# Main.net
KiCad netlist of a schematic drawn in Altium Designer
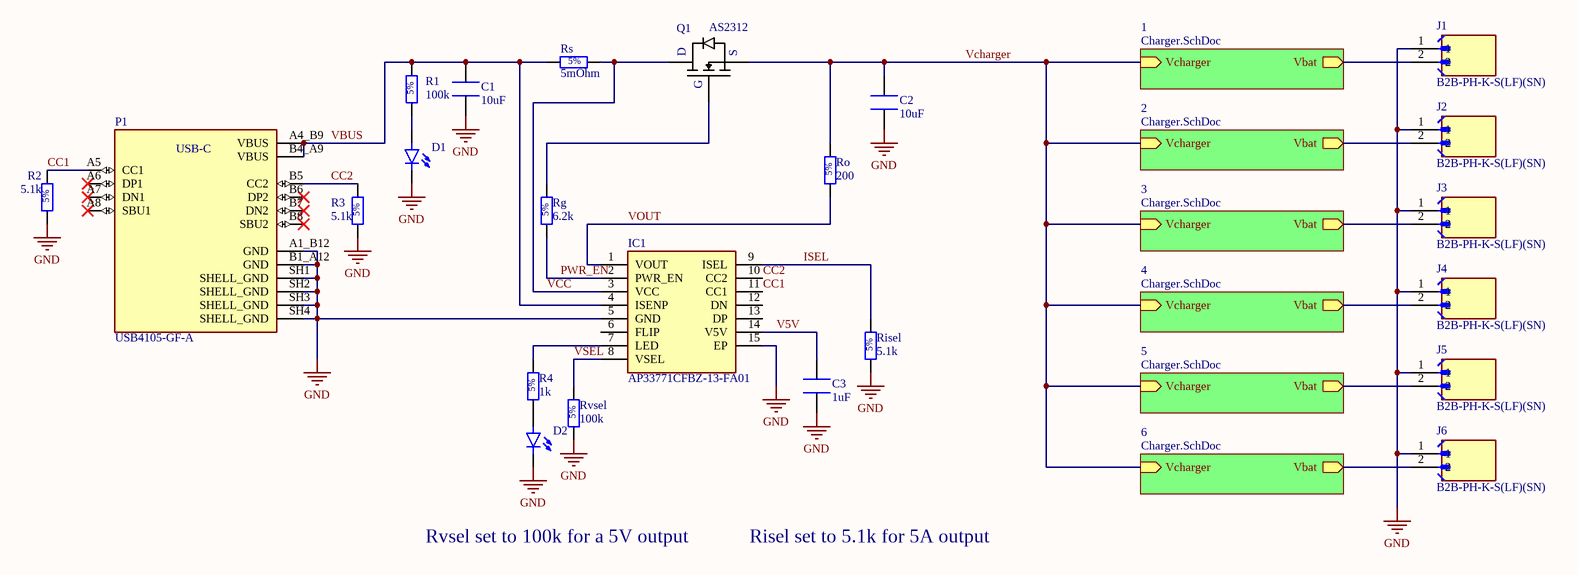
[diagram p0: Main.SchDoc]

(export (version "E")
  (design (tool "Eeschema 10.0.6"))
  (components
    (comp (ref "C1")
      (value "10uF")
      (footprint "APSS Flight Parts:CAPACITOR_0805_2012M-70N")
      (fields
        (field (name "TOLERANCE") "±20%")
        (field (name "MF PART NO.") "GRM21BR60J107ME15L")
        (field (name "APSS STANDARD PART") "APSS Standard")
      )
      (libsource (lib "APSS Flight Parts") (part "GRM21BR60J107ME15L"))
    )
    (comp (ref "C2")
      (value "10uF")
      (footprint "APSS Flight Parts:CAPACITOR_0805_2012M-70N")
      (fields
        (field (name "TOLERANCE") "±20%")
        (field (name "MF PART NO.") "GRM21BR60J107ME15L")
        (field (name "APSS STANDARD PART") "APSS Standard")
      )
      (libsource (lib "APSS Flight Parts") (part "GRM21BR60J107ME15L"))
    )
    (comp (ref "C3")
      (value "1uF")
      (footprint "APSS Flight Parts:CAPACITOR_0805_2012M-70N")
      (fields
        (field (name "TOLERANCE") "±20%")
        (field (name "MF PART NO.") "GRM21BR60J107ME15L")
        (field (name "APSS STANDARD PART") "APSS Standard")
      )
      (libsource (lib "APSS Flight Parts") (part "GRM21BR60J107ME15L"))
    )
    (comp (ref "D1")
      (value "LTST-C190 Series")
      (footprint "APSS Prototype Parts:LED_0603_1608M_0.80mm")
      (description "Diode - LED, 0603")
      (fields (field (name "APSS STANDARD PART") "APSS Standard"))
      (libsource (lib "APSS Prototype Parts") (part "LTST-C190 Series"))
    )
    (comp (ref "D2")
      (value "LTST-C190 Series")
      (footprint "APSS Prototype Parts:LED_0603_1608M_0.80mm")
      (description "Diode - LED, 0603")
      (fields (field (name "APSS STANDARD PART") "APSS Standard"))
      (libsource (lib "APSS Prototype Parts") (part "LTST-C190 Series"))
    )
    (comp (ref "IC1")
      (value "AP33771CFBZ-13-FA01")
      (footprint "AP33771CFBZ-13-FA01:AP33771CFBZ13FA01")
      (description "Integrated Circuit")
      (fields (field (name "MOUSER PART NUMBER") "621-P33771CFBZ13FA01"))
      (libsource (lib "AP33771CFBZ-13-FA01") (part "AP33771CFBZ-13-FA01"))
    )
    (comp (ref "J1")
      (value "B2B-PH-K-S(LF)(SN)")
      (footprint "JST_B2B-PH-K-S(LF)(SN)")
      (description "Connector Header Through Hole 2 position 0.079 (2.00mm)")
      (fields (field (name "MF") "JST") (field (name "MP") "B2B-PH-K-S (LF)(SN)"))
      (libsource (lib "B2B-PH-K-S(LF)(SN)") (part "B2B-PH-K-S(LF)(SN)"))
    )
    (comp (ref "J2")
      (value "B2B-PH-K-S(LF)(SN)")
      (footprint "JST_B2B-PH-K-S(LF)(SN)")
      (description "Connector Header Through Hole 2 position 0.079 (2.00mm)")
      (fields (field (name "MF") "JST") (field (name "MP") "B2B-PH-K-S (LF)(SN)"))
      (libsource (lib "B2B-PH-K-S(LF)(SN)") (part "B2B-PH-K-S(LF)(SN)"))
    )
    (comp (ref "J3")
      (value "B2B-PH-K-S(LF)(SN)")
      (footprint "JST_B2B-PH-K-S(LF)(SN)")
      (description "Connector Header Through Hole 2 position 0.079 (2.00mm)")
      (fields (field (name "MF") "JST") (field (name "MP") "B2B-PH-K-S (LF)(SN)"))
      (libsource (lib "B2B-PH-K-S(LF)(SN)") (part "B2B-PH-K-S(LF)(SN)"))
    )
    (comp (ref "J4")
      (value "B2B-PH-K-S(LF)(SN)")
      (footprint "JST_B2B-PH-K-S(LF)(SN)")
      (description "Connector Header Through Hole 2 position 0.079 (2.00mm)")
      (fields (field (name "MF") "JST") (field (name "MP") "B2B-PH-K-S (LF)(SN)"))
      (libsource (lib "B2B-PH-K-S(LF)(SN)") (part "B2B-PH-K-S(LF)(SN)"))
    )
    (comp (ref "J5")
      (value "B2B-PH-K-S(LF)(SN)")
      (footprint "JST_B2B-PH-K-S(LF)(SN)")
      (description "Connector Header Through Hole 2 position 0.079 (2.00mm)")
      (fields (field (name "MF") "JST") (field (name "MP") "B2B-PH-K-S (LF)(SN)"))
      (libsource (lib "B2B-PH-K-S(LF)(SN)") (part "B2B-PH-K-S(LF)(SN)"))
    )
    (comp (ref "J6")
      (value "B2B-PH-K-S(LF)(SN)")
      (footprint "JST_B2B-PH-K-S(LF)(SN)")
      (description "Connector Header Through Hole 2 position 0.079 (2.00mm)")
      (fields (field (name "MF") "JST") (field (name "MP") "B2B-PH-K-S (LF)(SN)"))
      (libsource (lib "B2B-PH-K-S(LF)(SN)") (part "B2B-PH-K-S(LF)(SN)"))
    )
    (comp (ref "P1")
      (value "USB4105-GF-A")
      (footprint "GCT_USB4105-GF-A")
      (libsource (lib "USB4105-GF-A") (part "USB4105-GF-A"))
    )
    (comp (ref "Q1")
      (value "AS2312")
      (footprint "APSS Prototype Parts:SOT23-3N-1.15mm")
      (description "Transistor - MOSFET, N-Channel AS2312")
      (fields (field (name "POWER") "1.2W") (field (name "APSS STANDARD PART") "APSS Standard"))
      (libsource (lib "APSS Prototype Parts") (part "AS2312"))
    )
    (comp (ref "R1")
      (value "100k")
      (footprint "APSS Flight Parts:Resistor_0805_2012M-50N")
      (fields
        (field (name "TOLERANCE") "5%")
        (field (name "POWER") "1/8W")
        (field (name "APSS STANDARD PART") "APSS Standard")
      )
      (libsource (lib "") (part "RMCF0805JT Series_1"))
    )
    (comp (ref "R2")
      (value "5.1k")
      (footprint "APSS Prototype Parts:Resistor_0805_2012M-50N")
      (fields
        (field (name "TOLERANCE") "5%")
        (field (name "POWER") "1/8W")
        (field (name "APSS STANDARD PART") "APSS Standard")
      )
      (libsource (lib "APSS Prototype Parts") (part "RMCF0805JT Series"))
    )
    (comp (ref "R3")
      (value "5.1k")
      (footprint "APSS Prototype Parts:Resistor_0805_2012M-50N")
      (fields
        (field (name "TOLERANCE") "5%")
        (field (name "POWER") "1/8W")
        (field (name "APSS STANDARD PART") "APSS Standard")
      )
      (libsource (lib "APSS Prototype Parts") (part "RMCF0805JT Series"))
    )
    (comp (ref "R4")
      (value "1k")
      (footprint "APSS Flight Parts:Resistor_0805_2012M-50N")
      (fields
        (field (name "TOLERANCE") "5%")
        (field (name "POWER") "1/8W")
        (field (name "APSS STANDARD PART") "APSS Standard")
      )
      (libsource (lib "") (part "RMCF0805JT Series_1"))
    )
    (comp (ref "Rg")
      (value "6.2k")
      (footprint "APSS Flight Parts:Resistor_0805_2012M-50N")
      (fields
        (field (name "TOLERANCE") "5%")
        (field (name "POWER") "1/8W")
        (field (name "APSS STANDARD PART") "APSS Standard")
      )
      (libsource (lib "") (part "RMCF0805JT Series_1"))
    )
    (comp (ref "Risel")
      (value "5.1k")
      (footprint "APSS Flight Parts:Resistor_0805_2012M-50N")
      (fields
        (field (name "TOLERANCE") "5%")
        (field (name "POWER") "1/8W")
        (field (name "APSS STANDARD PART") "APSS Standard")
      )
      (libsource (lib "") (part "RMCF0805JT Series_1"))
    )
    (comp (ref "Ro")
      (value "200")
      (footprint "APSS Flight Parts:Resistor_0805_2012M-50N")
      (fields
        (field (name "TOLERANCE") "5%")
        (field (name "POWER") "1/8W")
        (field (name "APSS STANDARD PART") "APSS Standard")
      )
      (libsource (lib "") (part "RMCF0805JT Series_1"))
    )
    (comp (ref "Rs")
      (value "5mOhm")
      (footprint "APSS Flight Parts:Resistor_0805_2012M-50N")
      (fields
        (field (name "TOLERANCE") "5%")
        (field (name "POWER") "1/8W")
        (field (name "APSS STANDARD PART") "APSS Standard")
      )
      (libsource (lib "APSS Flight Parts") (part "RMCF0805JT Series"))
    )
    (comp (ref "Rvsel")
      (value "100k")
      (footprint "APSS Flight Parts:Resistor_0805_2012M-50N")
      (fields
        (field (name "TOLERANCE") "5%")
        (field (name "POWER") "1/8W")
        (field (name "APSS STANDARD PART") "APSS Standard")
      )
      (libsource (lib "") (part "RMCF0805JT Series_1"))
    )
  )
  (nets
    (net (code "1") (name "/CC1") (class "Default")
      (node (ref "IC1") (pin "11") (pinfunction "CC1_11") (pintype "passive"))
      (node (ref "P1") (pin "A5") (pinfunction "CC1_A5") (pintype "bidirectional"))
      (node (ref "R2") (pin "2") (pinfunction "2_2") (pintype "passive"))
    )
    (net (code "2") (name "/CC2") (class "Default")
      (node (ref "IC1") (pin "10") (pinfunction "CC2_10") (pintype "passive"))
      (node (ref "P1") (pin "B5") (pinfunction "CC2_B5") (pintype "bidirectional"))
      (node (ref "R3") (pin "2") (pinfunction "2_2") (pintype "passive"))
    )
    (net (code "3") (name "/ISEL") (class "Default")
      (node (ref "IC1") (pin "9") (pinfunction "ISEL_9") (pintype "passive"))
      (node (ref "Risel") (pin "2") (pinfunction "2_2") (pintype "passive"))
    )
    (net (code "4") (name "/PWR_EN") (class "Default")
      (node (ref "IC1") (pin "2") (pinfunction "PWR_EN_2") (pintype "passive"))
      (node (ref "Rg") (pin "1") (pinfunction "1_1") (pintype "passive"))
    )
    (net (code "5") (name "/V5V") (class "Default")
      (node (ref "C3") (pin "2") (pinfunction "2_2") (pintype "passive"))
      (node (ref "IC1") (pin "14") (pinfunction "V5V_14") (pintype "passive"))
    )
    (net (code "6") (name "/VBUS") (class "Default")
      (node (ref "C1") (pin "2") (pinfunction "2_2") (pintype "passive"))
      (node (ref "IC1") (pin "4") (pinfunction "ISENP_4") (pintype "passive"))
      (node (ref "P1") (pin "A4_B9") (pinfunction "VBUS_A4_B9") (pintype "power_in"))
      (node (ref "P1") (pin "B4_A9") (pinfunction "VBUS_B4_A9") (pintype "power_in"))
      (node (ref "R1") (pin "2") (pinfunction "2_2") (pintype "passive"))
      (node (ref "Rs") (pin "1") (pinfunction "1_1") (pintype "passive"))
    )
    (net (code "7") (name "/VCC") (class "Default")
      (node (ref "IC1") (pin "3") (pinfunction "VCC_3") (pintype "passive"))
      (node (ref "Q1") (pin "3") (pinfunction "D_3") (pintype "passive"))
      (node (ref "Rs") (pin "2") (pinfunction "2_2") (pintype "passive"))
    )
    (net (code "8") (name "/VOUT") (class "Default")
      (node (ref "IC1") (pin "1") (pinfunction "VOUT_1") (pintype "passive"))
      (node (ref "Ro") (pin "1") (pinfunction "1_1") (pintype "passive"))
    )
    (net (code "9") (name "/VSEL") (class "Default")
      (node (ref "IC1") (pin "8") (pinfunction "VSEL_8") (pintype "passive"))
      (node (ref "Rvsel") (pin "2") (pinfunction "2_2") (pintype "passive"))
    )
    (net (code "10") (name "/Vbat") (class "Default")
      (node (ref "J6") (pin "2") (pinfunction "2_2") (pintype "passive"))
    )
    (net (code "11") (name "/Vbat_1") (class "Default")
      (node (ref "J4") (pin "2") (pinfunction "2_2") (pintype "passive"))
    )
    (net (code "12") (name "/Vbat_2") (class "Default")
      (node (ref "J3") (pin "2") (pinfunction "2_2") (pintype "passive"))
    )
    (net (code "13") (name "/Vbat_3") (class "Default")
      (node (ref "J5") (pin "2") (pinfunction "2_2") (pintype "passive"))
    )
    (net (code "14") (name "/Vbat_4") (class "Default")
      (node (ref "J2") (pin "2") (pinfunction "2_2") (pintype "passive"))
    )
    (net (code "15") (name "/Vbat_5") (class "Default")
      (node (ref "J1") (pin "2") (pinfunction "2_2") (pintype "passive"))
    )
    (net (code "16") (name "/Vcharger") (class "Default")
      (node (ref "C2") (pin "2") (pinfunction "2_2") (pintype "passive"))
      (node (ref "Q1") (pin "2") (pinfunction "S_2") (pintype "passive"))
      (node (ref "Ro") (pin "2") (pinfunction "2_2") (pintype "passive"))
    )
    (net (code "17") (name "GND") (class "Default")
      (node (ref "C1") (pin "1") (pinfunction "1_1") (pintype "passive"))
      (node (ref "C2") (pin "1") (pinfunction "1_1") (pintype "passive"))
      (node (ref "C3") (pin "1") (pinfunction "1_1") (pintype "passive"))
      (node (ref "D1") (pin "C") (pinfunction "C_C") (pintype "passive"))
      (node (ref "D2") (pin "C") (pinfunction "C_C") (pintype "passive"))
      (node (ref "IC1") (pin "15") (pinfunction "EP_15") (pintype "passive"))
      (node (ref "IC1") (pin "5") (pinfunction "GND_5") (pintype "passive"))
      (node (ref "J1") (pin "1") (pinfunction "1_1") (pintype "passive"))
      (node (ref "J2") (pin "1") (pinfunction "1_1") (pintype "passive"))
      (node (ref "J3") (pin "1") (pinfunction "1_1") (pintype "passive"))
      (node (ref "J4") (pin "1") (pinfunction "1_1") (pintype "passive"))
      (node (ref "J5") (pin "1") (pinfunction "1_1") (pintype "passive"))
      (node (ref "J6") (pin "1") (pinfunction "1_1") (pintype "passive"))
      (node (ref "P1") (pin "A1_B12") (pinfunction "GND_A1_B12") (pintype "power_in"))
      (node (ref "P1") (pin "B1_A12") (pinfunction "GND_B1_A12") (pintype "power_in"))
      (node (ref "P1") (pin "SH1") (pinfunction "SHELL_GND_SH1") (pintype "power_in"))
      (node (ref "P1") (pin "SH2") (pinfunction "SHELL_GND_SH2") (pintype "power_in"))
      (node (ref "P1") (pin "SH3") (pinfunction "SHELL_GND_SH3") (pintype "power_in"))
      (node (ref "P1") (pin "SH4") (pinfunction "SHELL_GND_SH4") (pintype "power_in"))
      (node (ref "R2") (pin "1") (pinfunction "1_1") (pintype "passive"))
      (node (ref "R3") (pin "1") (pinfunction "1_1") (pintype "passive"))
      (node (ref "Risel") (pin "1") (pinfunction "1_1") (pintype "passive"))
      (node (ref "Rvsel") (pin "1") (pinfunction "1_1") (pintype "passive"))
    )
    (net (code "18") (name "Net-(D1-PadA)") (class "Default")
      (node (ref "D1") (pin "A") (pinfunction "A_A") (pintype "passive"))
      (node (ref "R1") (pin "1") (pinfunction "1_1") (pintype "passive"))
    )
    (net (code "19") (name "Net-(D2-PadA)") (class "Default")
      (node (ref "D2") (pin "A") (pinfunction "A_A") (pintype "passive"))
      (node (ref "R4") (pin "1") (pinfunction "1_1") (pintype "passive"))
    )
    (net (code "20") (name "Net-(IC1-LED)") (class "Default")
      (node (ref "IC1") (pin "7") (pinfunction "LED_7") (pintype "passive"))
      (node (ref "R4") (pin "2") (pinfunction "2_2") (pintype "passive"))
    )
    (net (code "21") (name "Net-(Q1-G)") (class "Default")
      (node (ref "Q1") (pin "1") (pinfunction "G_1") (pintype "passive"))
      (node (ref "Rg") (pin "2") (pinfunction "2_2") (pintype "passive"))
    )
    (net (code "22") (name "unconnected-(IC1-DN-Pad12)") (class "Default")
      (node (ref "IC1") (pin "12") (pinfunction "DN_12") (pintype "passive"))
    )
    (net (code "23") (name "unconnected-(IC1-DP-Pad13)") (class "Default")
      (node (ref "IC1") (pin "13") (pinfunction "DP_13") (pintype "passive"))
    )
    (net (code "24") (name "unconnected-(IC1-FLIP-Pad6)") (class "Default")
      (node (ref "IC1") (pin "6") (pinfunction "FLIP_6") (pintype "passive"))
    )
    (net (code "25") (name "unconnected-(P1-DN1-PadA7)") (class "Default")
      (node (ref "P1") (pin "A7") (pinfunction "DN1_A7") (pintype "bidirectional+no_connect"))
    )
    (net (code "26") (name "unconnected-(P1-DN2-PadB7)") (class "Default")
      (node (ref "P1") (pin "B7") (pinfunction "DN2_B7") (pintype "bidirectional+no_connect"))
    )
    (net (code "27") (name "unconnected-(P1-DP1-PadA6)") (class "Default")
      (node (ref "P1") (pin "A6") (pinfunction "DP1_A6") (pintype "bidirectional+no_connect"))
    )
    (net (code "28") (name "unconnected-(P1-DP2-PadB6)") (class "Default")
      (node (ref "P1") (pin "B6") (pinfunction "DP2_B6") (pintype "bidirectional+no_connect"))
    )
    (net (code "29") (name "unconnected-(P1-SBU1-PadA8)") (class "Default")
      (node (ref "P1") (pin "A8") (pinfunction "SBU1_A8") (pintype "bidirectional+no_connect"))
    )
    (net (code "30") (name "unconnected-(P1-SBU2-PadB8)") (class "Default")
      (node (ref "P1") (pin "B8") (pinfunction "SBU2_B8") (pintype "bidirectional+no_connect"))
    )
  )
)
